# Split_propu2026.net
KiCad netlist of a schematic drawn in Altium Designer
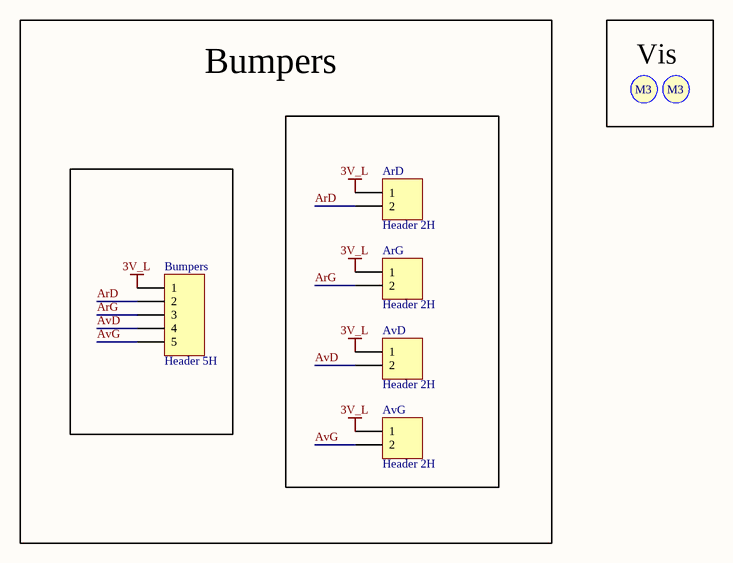
[diagram p0: Split_propu2026.SchDoc]

(export (version "E")
  (design (tool "Eeschema 10.0.6"))
  (components
    (comp (ref "ArD")
      (value "Header 2H")
      (footprint "S2B-XH-A")
      (description "Header, 2-Pin, Right Angle")
      (fields (field (name "PUBLISHER") "Altium Limited"))
      (libsource (lib "Miscellaneous Connectors") (part "Header 2H"))
    )
    (comp (ref "ArG")
      (value "Header 2H")
      (footprint "S2B-XH-A")
      (description "Header, 2-Pin, Right Angle")
      (fields (field (name "PUBLISHER") "Altium Limited"))
      (libsource (lib "Miscellaneous Connectors") (part "Header 2H"))
    )
    (comp (ref "AvD")
      (value "Header 2H")
      (footprint "S2B-XH-A")
      (description "Header, 2-Pin, Right Angle")
      (fields (field (name "PUBLISHER") "Altium Limited"))
      (libsource (lib "Miscellaneous Connectors") (part "Header 2H"))
    )
    (comp (ref "AvG")
      (value "Header 2H")
      (footprint "S2B-XH-A")
      (description "Header, 2-Pin, Right Angle")
      (fields (field (name "PUBLISHER") "Altium Limited"))
      (libsource (lib "Miscellaneous Connectors") (part "Header 2H"))
    )
    (comp (ref "Bumpers")
      (value "Header 5H")
      (footprint "S5B-XH-A")
      (description "Header, 5-Pin, Right Angle")
      (fields (field (name "PUBLISHER") "Altium Limited"))
      (libsource (lib "Miscellaneous Connectors") (part "Header 5H"))
    )
    (comp (ref "S0")
      (value "Screw M3")
      (footprint "Screw M3")
      (libsource (lib "Robot_2019") (part "Screw M3"))
    )
    (comp (ref "S1")
      (value "Screw M3")
      (footprint "Screw M3")
      (libsource (lib "Robot_2019") (part "Screw M3"))
    )
  )
  (nets
    (net (code "1") (name "/ArD") (class "Default")
      (node (ref "ArD") (pin "2") (pinfunction "2_2") (pintype "passive"))
      (node (ref "Bumpers") (pin "2") (pinfunction "2_2") (pintype "passive"))
    )
    (net (code "2") (name "/ArG") (class "Default")
      (node (ref "ArG") (pin "2") (pinfunction "2_2") (pintype "passive"))
      (node (ref "Bumpers") (pin "3") (pinfunction "3_3") (pintype "passive"))
    )
    (net (code "3") (name "/AvD") (class "Default")
      (node (ref "AvD") (pin "2") (pinfunction "2_2") (pintype "passive"))
      (node (ref "Bumpers") (pin "4") (pinfunction "4_4") (pintype "passive"))
    )
    (net (code "4") (name "/AvG") (class "Default")
      (node (ref "AvG") (pin "2") (pinfunction "2_2") (pintype "passive"))
      (node (ref "Bumpers") (pin "5") (pinfunction "5_5") (pintype "passive"))
    )
    (net (code "5") (name "3V_L") (class "Default")
      (node (ref "ArD") (pin "1") (pinfunction "1_1") (pintype "passive"))
      (node (ref "ArG") (pin "1") (pinfunction "1_1") (pintype "passive"))
      (node (ref "AvD") (pin "1") (pinfunction "1_1") (pintype "passive"))
      (node (ref "AvG") (pin "1") (pinfunction "1_1") (pintype "passive"))
      (node (ref "Bumpers") (pin "1") (pinfunction "1_1") (pintype "passive"))
    )
  )
)
